# UWB_F3_MCU.net
KiCad netlist of a schematic drawn in Altium Designer
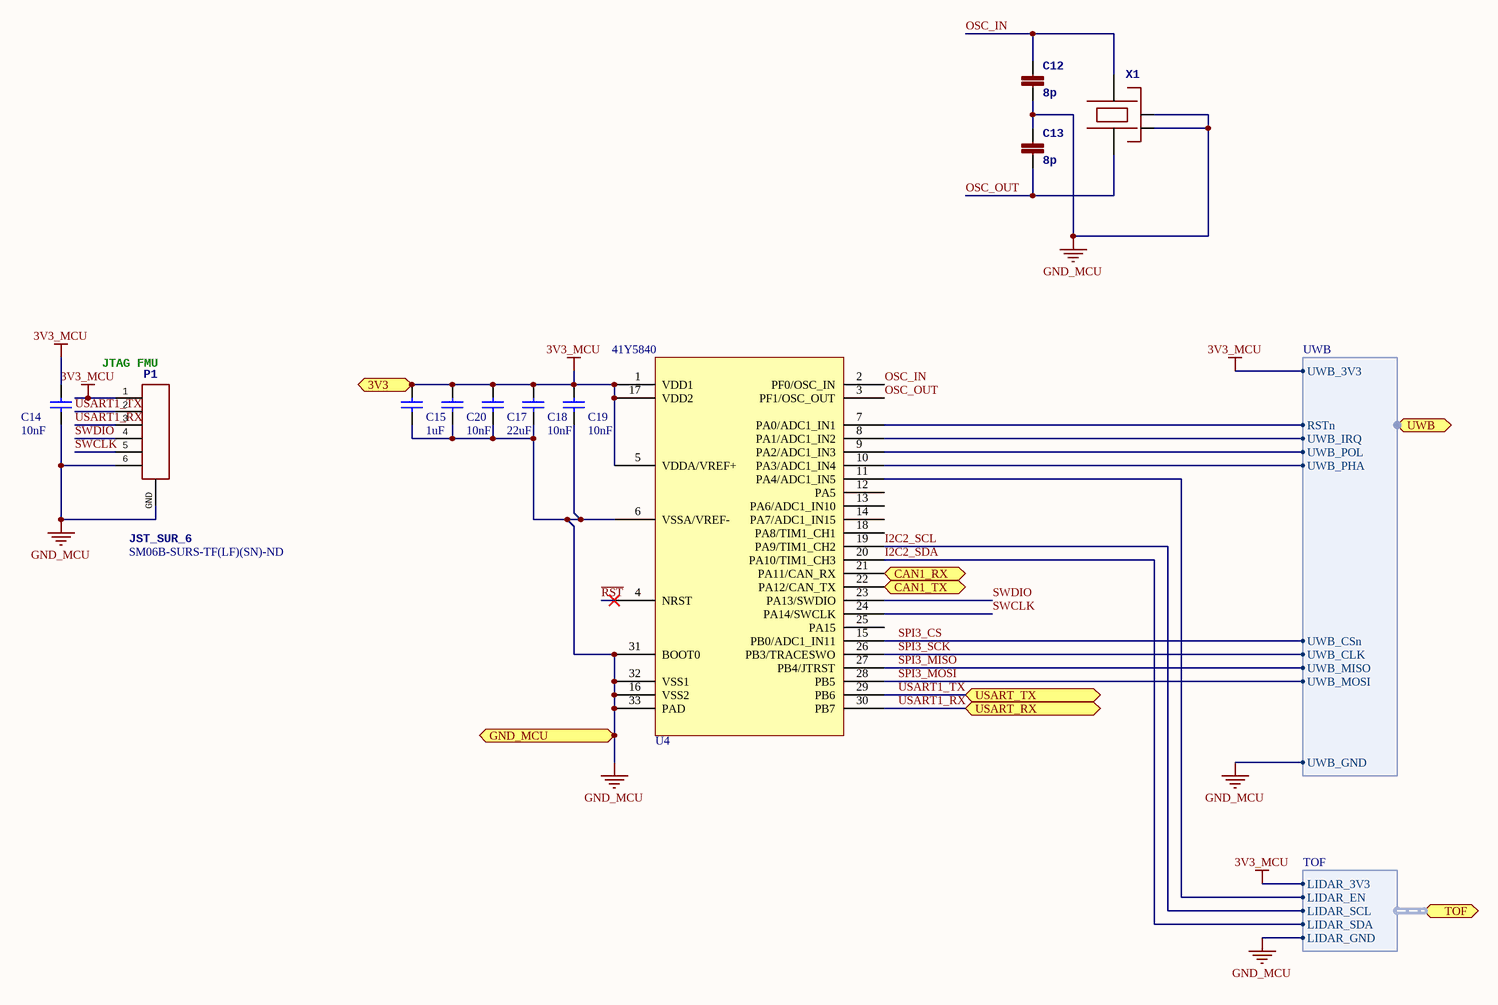
[diagram p0: UWB_F3_MCU.SchDoc]

(export (version "E")
  (design (tool "Eeschema 10.0.6"))
  (components
    (comp (ref "C12")
      (value "8p")
      (footprint "0201-cap")
      (description "CAP CER 8PF 50V NP0 0201")
      (libsource (lib "OMD") (part "CAP0402"))
    )
    (comp (ref "C13")
      (value "8p")
      (footprint "0201-cap")
      (description "CAP CER 8PF 50V NP0 0201")
      (libsource (lib "OMD") (part "CAP0402"))
    )
    (comp (ref "C14")
      (value "10nF")
      (footprint "CAPC1005L")
      (description "CAP CER 10000PF 50V X7R 0402")
      (libsource (lib "OMD") (part "Cap"))
    )
    (comp (ref "C15")
      (value "1uF")
      (footprint "CAPC1005L")
      (description "CAP CER 1UF 6.3V X5R 0402")
      (fields (field (name "Comment") "Cap"))
      (libsource (lib "OMD") (part "Cap"))
    )
    (comp (ref "C17")
      (value "22uF")
      (footprint "CAPC2012L")
      (description "Capacitor")
      (fields (field (name "Comment") "Cap"))
      (libsource (lib "OMD") (part "Cap"))
    )
    (comp (ref "C18")
      (value "10nF")
      (footprint "CAPC1005L")
      (description "CAP CER 10000PF 50V X7R 0402")
      (libsource (lib "OMD") (part "Cap"))
    )
    (comp (ref "C19")
      (value "10nF")
      (footprint "CAPC1005L")
      (description "CAP CER 10000PF 50V X7R 0402")
      (libsource (lib "OMD") (part "Cap"))
    )
    (comp (ref "C20")
      (value "10nF")
      (footprint "CAPC1005L")
      (description "CAP CER 10000PF 50V X7R 0402")
      (libsource (lib "OMD") (part "Cap"))
    )
    (comp (ref "P1")
      (value "JST_SUR_6")
      (footprint "JST_SUR_H6")
      (description "Connector, Header, 6Pos, .8mm IDC, R/A, SMD, Tin")
      (fields (field (name "SUPPLIER PART NUMBER 1") "SM06B-SURS-TF(LF)(SN)-ND"))
      (libsource (lib "OMD") (part "JST_SUR_6"))
    )
    (comp (ref "U4")
      (value "IC MCU M4 64KB FLASH 32UFQFPN")
      (footprint "QFN50P500X500X60-32L")
      (description "72 MHz Cortex-M4F MCU with 16 KB RAM, 64 KB flash")
      (fields (field (name "SUPPLIER PART NUMBER 1") "41Y5840"))
      (libsource (lib "OMD") (part "STM32F302K8U6"))
    )
    (comp (ref "X1")
      (value "Crystal Oscillator in SMD 1.6 x 1.2")
      (footprint "OSCILLATOR-1.6x1.2")
      (description "CRYSTAL 24MHZ 8PF SMD")
      (libsource (lib "OMD") (part "OSCILLATOR-3.2X2.5"))
    )
  )
  (nets
    (net (code "3") (name "/CAN1_RX") (class "Default")
      (node (ref "U4") (pin "21") (pinfunction "PA11/CAN_RX_21") (pintype "passive"))
    )
    (net (code "4") (name "/CAN1_TX") (class "Default")
      (node (ref "U4") (pin "22") (pinfunction "PA12/CAN_TX_22") (pintype "passive"))
    )
    (net (code "5") (name "/I2C2_SCL") (class "Default")
      (node (ref "U4") (pin "19") (pinfunction "PA9/TIM1_CH2_19") (pintype "passive"))
    )
    (net (code "6") (name "/I2C2_SDA") (class "Default")
      (node (ref "U4") (pin "20") (pinfunction "PA10/TIM1_CH3_20") (pintype "passive"))
    )
    (net (code "7") (name "/LIDAR_EN") (class "Default")
      (node (ref "U4") (pin "11") (pinfunction "PA4/ADC1_IN5_11") (pintype "passive"))
    )
    (net (code "8") (name "/OSC_IN") (class "Default")
      (node (ref "C12") (pin "1") (pinfunction "1_1") (pintype "passive"))
      (node (ref "U4") (pin "2") (pinfunction "PF0/OSC_IN_2") (pintype "passive"))
      (node (ref "X1") (pin "3") (pinfunction "3_3") (pintype "passive"))
    )
    (net (code "9") (name "/OSC_OUT") (class "Default")
      (node (ref "C13") (pin "2") (pinfunction "2_2") (pintype "passive"))
      (node (ref "U4") (pin "3") (pinfunction "PF1/OSC_OUT_3") (pintype "passive"))
      (node (ref "X1") (pin "1") (pinfunction "1_1") (pintype "passive"))
    )
    (net (code "10") (name "/RSTn") (class "Default")
      (node (ref "U4") (pin "7") (pinfunction "PA0/ADC1_IN1_7") (pintype "passive"))
    )
    (net (code "11") (name "/SPI3_CS") (class "Default")
      (node (ref "U4") (pin "15") (pinfunction "PB0/ADC1_IN11_15") (pintype "passive"))
    )
    (net (code "12") (name "/SPI3_MISO") (class "Default")
      (node (ref "U4") (pin "27") (pinfunction "PB4/JTRST_27") (pintype "passive"))
    )
    (net (code "13") (name "/SPI3_MOSI") (class "Default")
      (node (ref "U4") (pin "28") (pinfunction "PB5_28") (pintype "passive"))
    )
    (net (code "14") (name "/SPI3_SCK") (class "Default")
      (node (ref "U4") (pin "26") (pinfunction "PB3/TRACESWO_26") (pintype "passive"))
    )
    (net (code "15") (name "/SWCLK") (class "Default")
      (node (ref "P1") (pin "5") (pinfunction "5_5") (pintype "passive"))
      (node (ref "U4") (pin "24") (pinfunction "PA14/SWCLK_24") (pintype "passive"))
    )
    (net (code "16") (name "/SWDIO") (class "Default")
      (node (ref "P1") (pin "4") (pinfunction "4_4") (pintype "passive"))
      (node (ref "U4") (pin "23") (pinfunction "PA13/SWDIO_23") (pintype "passive"))
    )
    (net (code "17") (name "/USART1_RX") (class "Default")
      (node (ref "P1") (pin "3") (pinfunction "3_3") (pintype "passive"))
      (node (ref "U4") (pin "30") (pinfunction "PB7_30") (pintype "passive"))
    )
    (net (code "18") (name "/USART1_TX") (class "Default")
      (node (ref "P1") (pin "2") (pinfunction "2_2") (pintype "passive"))
      (node (ref "U4") (pin "29") (pinfunction "PB6_29") (pintype "passive"))
    )
    (net (code "19") (name "/UWB_IRQ") (class "Default")
      (node (ref "U4") (pin "8") (pinfunction "PA1/ADC1_IN2_8") (pintype "passive"))
    )
    (net (code "20") (name "/UWB_PHA") (class "Default")
      (node (ref "U4") (pin "10") (pinfunction "PA3/ADC1_IN4_10") (pintype "passive"))
    )
    (net (code "21") (name "/UWB_POL") (class "Default")
      (node (ref "U4") (pin "9") (pinfunction "PA2/ADC1_IN3_9") (pintype "passive"))
    )
    (net (code "24") (name "/~{RST}") (class "Default")
      (node (ref "U4") (pin "4") (pinfunction "NRST_4") (pintype "passive+no_connect"))
    )
    (net (code "25") (name "3V3_MCU") (class "Default")
      (node (ref "C14") (pin "2") (pinfunction "2_2") (pintype "passive"))
      (node (ref "C15") (pin "1") (pinfunction "1_1") (pintype "passive"))
      (node (ref "C17") (pin "2") (pinfunction "2_2") (pintype "passive"))
      (node (ref "C18") (pin "2") (pinfunction "2_2") (pintype "passive"))
      (node (ref "C19") (pin "2") (pinfunction "2_2") (pintype "passive"))
      (node (ref "C20") (pin "2") (pinfunction "2_2") (pintype "passive"))
      (node (ref "P1") (pin "1") (pinfunction "1_1") (pintype "passive"))
      (node (ref "U4") (pin "1") (pinfunction "VDD1_1") (pintype "passive"))
      (node (ref "U4") (pin "17") (pinfunction "VDD2_17") (pintype "passive"))
      (node (ref "U4") (pin "5") (pinfunction "VDDA/VREF+_5") (pintype "passive"))
    )
    (net (code "26") (name "GND_MCU") (class "Default")
      (node (ref "C12") (pin "2") (pinfunction "2_2") (pintype "passive"))
      (node (ref "C13") (pin "1") (pinfunction "1_1") (pintype "passive"))
      (node (ref "C14") (pin "1") (pinfunction "1_1") (pintype "passive"))
      (node (ref "C15") (pin "2") (pinfunction "2_2") (pintype "passive"))
      (node (ref "C17") (pin "1") (pinfunction "1_1") (pintype "passive"))
      (node (ref "C18") (pin "1") (pinfunction "1_1") (pintype "passive"))
      (node (ref "C19") (pin "1") (pinfunction "1_1") (pintype "passive"))
      (node (ref "C20") (pin "1") (pinfunction "1_1") (pintype "passive"))
      (node (ref "P1") (pin "6") (pinfunction "6_6") (pintype "passive"))
      (node (ref "P1") (pin "GND") (pinfunction "GND_GND") (pintype "passive"))
      (node (ref "U4") (pin "16") (pinfunction "VSS2_16") (pintype "passive"))
      (node (ref "U4") (pin "31") (pinfunction "BOOT0_31") (pintype "passive"))
      (node (ref "U4") (pin "32") (pinfunction "VSS1_32") (pintype "passive"))
      (node (ref "U4") (pin "33") (pinfunction "PAD_33") (pintype "passive"))
      (node (ref "U4") (pin "6") (pinfunction "VSSA/VREF-_6") (pintype "passive"))
      (node (ref "X1") (pin "2") (pinfunction "NC_2_2") (pintype "open_emitter"))
      (node (ref "X1") (pin "4") (pinfunction "NC_4_4") (pintype "open_emitter"))
    )
    (net (code "27") (name "unconnected-(U4-PA5-Pad12)") (class "Default")
      (node (ref "U4") (pin "12") (pinfunction "PA5_12") (pintype "passive"))
    )
    (net (code "28") (name "unconnected-(U4-PA6{slash}ADC1_IN10-Pad13)") (class "Default")
      (node (ref "U4") (pin "13") (pinfunction "PA6/ADC1_IN10_13") (pintype "passive"))
    )
    (net (code "29") (name "unconnected-(U4-PA7{slash}ADC1_IN15-Pad14)") (class "Default")
      (node (ref "U4") (pin "14") (pinfunction "PA7/ADC1_IN15_14") (pintype "passive"))
    )
    (net (code "30") (name "unconnected-(U4-PA8{slash}TIM1_CH1-Pad18)") (class "Default")
      (node (ref "U4") (pin "18") (pinfunction "PA8/TIM1_CH1_18") (pintype "passive"))
    )
    (net (code "31") (name "unconnected-(U4-PA15-Pad25)") (class "Default")
      (node (ref "U4") (pin "25") (pinfunction "PA15_25") (pintype "passive"))
    )
  )
)
